# big_seven_v0_2.net
KiCad netlist of a schematic drawn in EAGLE
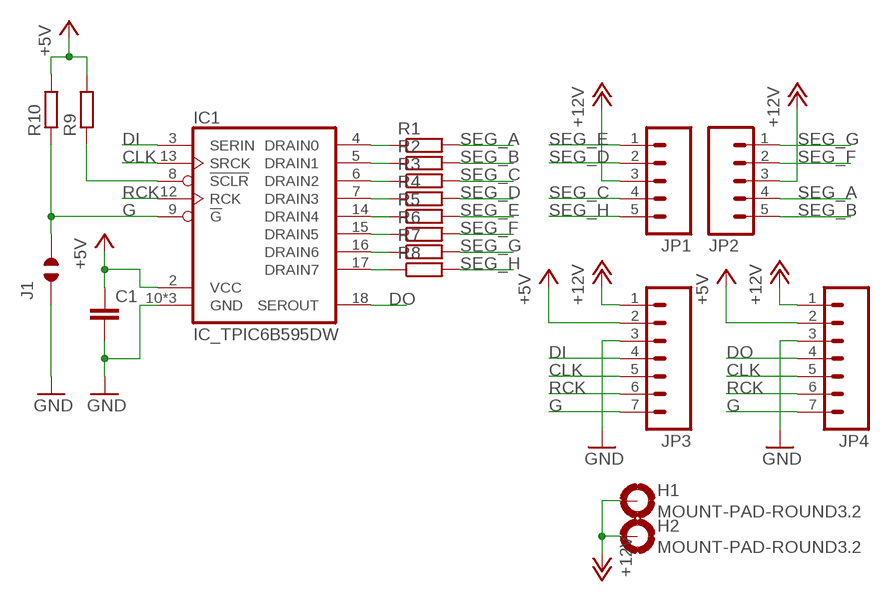
[diagram p0: schematic, sheet 1]

(export (version "E")
  (design (tool "Eeschema 10.0.6"))
  (components
    (comp (ref "C1")
      (value "C-EUC0805")
      (footprint "eagle-import:C0805")
      (libsource (lib "eagle-import") (part "C-EUC0805"))
    )
    (comp (ref "H1")
      (value "MOUNT-PAD-ROUND3.2")
      (footprint "eagle-import:3,2-PAD")
      (libsource (lib "eagle-import") (part "MOUNT-PAD-ROUND3.2"))
    )
    (comp (ref "H2")
      (value "MOUNT-PAD-ROUND3.2")
      (footprint "eagle-import:3,2-PAD")
      (libsource (lib "eagle-import") (part "MOUNT-PAD-ROUND3.2"))
    )
    (comp (ref "IC1")
      (value "IC_TPIC6B595DW")
      (footprint "eagle-import:SOIC-20")
      (libsource (lib "eagle-import") (part "IC_TPIC6B595DW"))
    )
    (comp (ref "J1")
      (value "JUMPER_SOLDER_1X2")
      (footprint "eagle-import:JUMPER_SOLDER_1X2")
      (libsource (lib "eagle-import") (part "JUMPER_SOLDER_1X2"))
    )
    (comp (ref "JP1")
      (value "M05PTH")
      (footprint "eagle-import:1X05")
      (libsource (lib "eagle-import") (part "M05PTH"))
    )
    (comp (ref "JP2")
      (value "M05PTH")
      (footprint "eagle-import:1X05")
      (libsource (lib "eagle-import") (part "M05PTH"))
    )
    (comp (ref "JP3")
      (value "M07LONGPADS")
      (footprint "eagle-import:1X07_LONGPADS")
      (libsource (lib "eagle-import") (part "M07LONGPADS"))
    )
    (comp (ref "JP4")
      (value "M07LONGPADS")
      (footprint "eagle-import:1X07_LONGPADS")
      (libsource (lib "eagle-import") (part "M07LONGPADS"))
    )
    (comp (ref "R1")
      (value "R-EU_M1206")
      (footprint "eagle-import:M1206")
      (libsource (lib "eagle-import") (part "R-EU_M1206"))
    )
    (comp (ref "R2")
      (value "R-EU_M1206")
      (footprint "eagle-import:M1206")
      (libsource (lib "eagle-import") (part "R-EU_M1206"))
    )
    (comp (ref "R3")
      (value "R-EU_M1206")
      (footprint "eagle-import:M1206")
      (libsource (lib "eagle-import") (part "R-EU_M1206"))
    )
    (comp (ref "R4")
      (value "R-EU_M1206")
      (footprint "eagle-import:M1206")
      (libsource (lib "eagle-import") (part "R-EU_M1206"))
    )
    (comp (ref "R5")
      (value "R-EU_M1206")
      (footprint "eagle-import:M1206")
      (libsource (lib "eagle-import") (part "R-EU_M1206"))
    )
    (comp (ref "R6")
      (value "R-EU_M1206")
      (footprint "eagle-import:M1206")
      (libsource (lib "eagle-import") (part "R-EU_M1206"))
    )
    (comp (ref "R7")
      (value "R-EU_M1206")
      (footprint "eagle-import:M1206")
      (libsource (lib "eagle-import") (part "R-EU_M1206"))
    )
    (comp (ref "R8")
      (value "R-EU_M1206")
      (footprint "eagle-import:M1206")
      (libsource (lib "eagle-import") (part "R-EU_M1206"))
    )
    (comp (ref "R9")
      (value "R-EU_M0805")
      (footprint "eagle-import:M0805")
      (libsource (lib "eagle-import") (part "R-EU_M0805"))
    )
    (comp (ref "R10")
      (value "R-EU_M0805")
      (footprint "eagle-import:M0805")
      (libsource (lib "eagle-import") (part "R-EU_M0805"))
    )
  )
  (nets
    (net (code "1") (name "+5V") (class "Default")
      (node (ref "C1") (pin "1") (pinfunction "1_1") (pintype "passive"))
      (node (ref "IC1") (pin "2") (pinfunction "VCC_2") (pintype "power_in"))
      (node (ref "JP3") (pin "2") (pinfunction "2_2") (pintype "passive"))
      (node (ref "JP4") (pin "2") (pinfunction "2_2") (pintype "passive"))
      (node (ref "R10") (pin "2") (pinfunction "2_2") (pintype "passive"))
      (node (ref "R9") (pin "2") (pinfunction "2_2") (pintype "passive"))
    )
    (net (code "2") (name "+12V") (class "Default")
      (node (ref "H1") (pin "B3,2") (pinfunction "MOUNT_B3,2") (pintype "passive"))
      (node (ref "H2") (pin "B3,2") (pinfunction "MOUNT_B3,2") (pintype "passive"))
      (node (ref "JP1") (pin "3") (pinfunction "3_3") (pintype "passive"))
      (node (ref "JP2") (pin "3") (pinfunction "3_3") (pintype "passive"))
      (node (ref "JP3") (pin "1") (pinfunction "1_1") (pintype "passive"))
      (node (ref "JP4") (pin "1") (pinfunction "1_1") (pintype "passive"))
    )
    (net (code "3") (name "/CLK") (class "Default")
      (node (ref "IC1") (pin "13") (pinfunction "SRCK_13") (pintype "input"))
      (node (ref "JP3") (pin "5") (pinfunction "5_5") (pintype "passive"))
      (node (ref "JP4") (pin "5") (pinfunction "5_5") (pintype "passive"))
    )
    (net (code "4") (name "/DI") (class "Default")
      (node (ref "IC1") (pin "3") (pinfunction "SERIN_3") (pintype "input"))
      (node (ref "JP3") (pin "4") (pinfunction "4_4") (pintype "passive"))
    )
    (net (code "5") (name "/DO") (class "Default")
      (node (ref "IC1") (pin "18") (pinfunction "SEROUT_18") (pintype "output"))
      (node (ref "JP4") (pin "4") (pinfunction "4_4") (pintype "passive"))
    )
    (net (code "6") (name "/G") (class "Default")
      (node (ref "IC1") (pin "9") (pinfunction "~{G}_9") (pintype "input"))
      (node (ref "J1") (pin "2") (pinfunction "2_2") (pintype "passive"))
      (node (ref "JP3") (pin "7") (pinfunction "7_7") (pintype "passive"))
      (node (ref "JP4") (pin "7") (pinfunction "7_7") (pintype "passive"))
      (node (ref "R10") (pin "1") (pinfunction "1_1") (pintype "passive"))
    )
    (net (code "7") (name "/RCK") (class "Default")
      (node (ref "IC1") (pin "12") (pinfunction "RCK_12") (pintype "input"))
      (node (ref "JP3") (pin "6") (pinfunction "6_6") (pintype "passive"))
      (node (ref "JP4") (pin "6") (pinfunction "6_6") (pintype "passive"))
    )
    (net (code "8") (name "/SEG_A") (class "Default")
      (node (ref "JP2") (pin "4") (pinfunction "4_4") (pintype "passive"))
      (node (ref "R1") (pin "2") (pinfunction "2_2") (pintype "passive"))
    )
    (net (code "9") (name "/SEG_B") (class "Default")
      (node (ref "JP2") (pin "5") (pinfunction "5_5") (pintype "passive"))
      (node (ref "R2") (pin "2") (pinfunction "2_2") (pintype "passive"))
    )
    (net (code "10") (name "/SEG_C") (class "Default")
      (node (ref "JP1") (pin "4") (pinfunction "4_4") (pintype "passive"))
      (node (ref "R3") (pin "2") (pinfunction "2_2") (pintype "passive"))
    )
    (net (code "11") (name "/SEG_D") (class "Default")
      (node (ref "JP1") (pin "2") (pinfunction "2_2") (pintype "passive"))
      (node (ref "R4") (pin "2") (pinfunction "2_2") (pintype "passive"))
    )
    (net (code "12") (name "/SEG_E") (class "Default")
      (node (ref "JP1") (pin "1") (pinfunction "1_1") (pintype "passive"))
      (node (ref "R5") (pin "2") (pinfunction "2_2") (pintype "passive"))
    )
    (net (code "13") (name "/SEG_F") (class "Default")
      (node (ref "JP2") (pin "2") (pinfunction "2_2") (pintype "passive"))
      (node (ref "R6") (pin "2") (pinfunction "2_2") (pintype "passive"))
    )
    (net (code "14") (name "/SEG_G") (class "Default")
      (node (ref "JP2") (pin "1") (pinfunction "1_1") (pintype "passive"))
      (node (ref "R7") (pin "2") (pinfunction "2_2") (pintype "passive"))
    )
    (net (code "15") (name "/SEG_H") (class "Default")
      (node (ref "JP1") (pin "5") (pinfunction "5_5") (pintype "passive"))
      (node (ref "R8") (pin "2") (pinfunction "2_2") (pintype "passive"))
    )
    (net (code "16") (name "GND") (class "Default")
      (node (ref "C1") (pin "2") (pinfunction "2_2") (pintype "passive"))
      (node (ref "IC1") (pin "10") (pinfunction "GND_10") (pintype "power_in"))
      (node (ref "IC1") (pin "11") (pinfunction "GND_11") (pintype "power_in"))
      (node (ref "IC1") (pin "19") (pinfunction "GND_19") (pintype "power_in"))
      (node (ref "J1") (pin "1") (pinfunction "1_1") (pintype "passive"))
      (node (ref "JP3") (pin "3") (pinfunction "3_3") (pintype "passive"))
      (node (ref "JP4") (pin "3") (pinfunction "3_3") (pintype "passive"))
    )
    (net (code "17") (name "Net-(IC1-DRAIN0)") (class "Default")
      (node (ref "IC1") (pin "4") (pinfunction "DRAIN0_4") (pintype "output"))
      (node (ref "R1") (pin "1") (pinfunction "1_1") (pintype "passive"))
    )
    (net (code "18") (name "Net-(IC1-DRAIN1)") (class "Default")
      (node (ref "IC1") (pin "5") (pinfunction "DRAIN1_5") (pintype "output"))
      (node (ref "R2") (pin "1") (pinfunction "1_1") (pintype "passive"))
    )
    (net (code "19") (name "Net-(IC1-DRAIN2)") (class "Default")
      (node (ref "IC1") (pin "6") (pinfunction "DRAIN2_6") (pintype "output"))
      (node (ref "R3") (pin "1") (pinfunction "1_1") (pintype "passive"))
    )
    (net (code "20") (name "Net-(IC1-DRAIN3)") (class "Default")
      (node (ref "IC1") (pin "7") (pinfunction "DRAIN3_7") (pintype "output"))
      (node (ref "R4") (pin "1") (pinfunction "1_1") (pintype "passive"))
    )
    (net (code "21") (name "Net-(IC1-DRAIN4)") (class "Default")
      (node (ref "IC1") (pin "14") (pinfunction "DRAIN4_14") (pintype "output"))
      (node (ref "R5") (pin "1") (pinfunction "1_1") (pintype "passive"))
    )
    (net (code "22") (name "Net-(IC1-DRAIN5)") (class "Default")
      (node (ref "IC1") (pin "15") (pinfunction "DRAIN5_15") (pintype "output"))
      (node (ref "R6") (pin "1") (pinfunction "1_1") (pintype "passive"))
    )
    (net (code "23") (name "Net-(IC1-DRAIN6)") (class "Default")
      (node (ref "IC1") (pin "16") (pinfunction "DRAIN6_16") (pintype "output"))
      (node (ref "R7") (pin "1") (pinfunction "1_1") (pintype "passive"))
    )
    (net (code "24") (name "Net-(IC1-DRAIN7)") (class "Default")
      (node (ref "IC1") (pin "17") (pinfunction "DRAIN7_17") (pintype "output"))
      (node (ref "R8") (pin "1") (pinfunction "1_1") (pintype "passive"))
    )
    (net (code "25") (name "Net-(IC1-~{SCLR})") (class "Default")
      (node (ref "IC1") (pin "8") (pinfunction "~{SCLR}_8") (pintype "input"))
      (node (ref "R9") (pin "1") (pinfunction "1_1") (pintype "passive"))
    )
  )
)
